# ver061_Power.net
KiCad netlist of a schematic drawn in Altium Designer
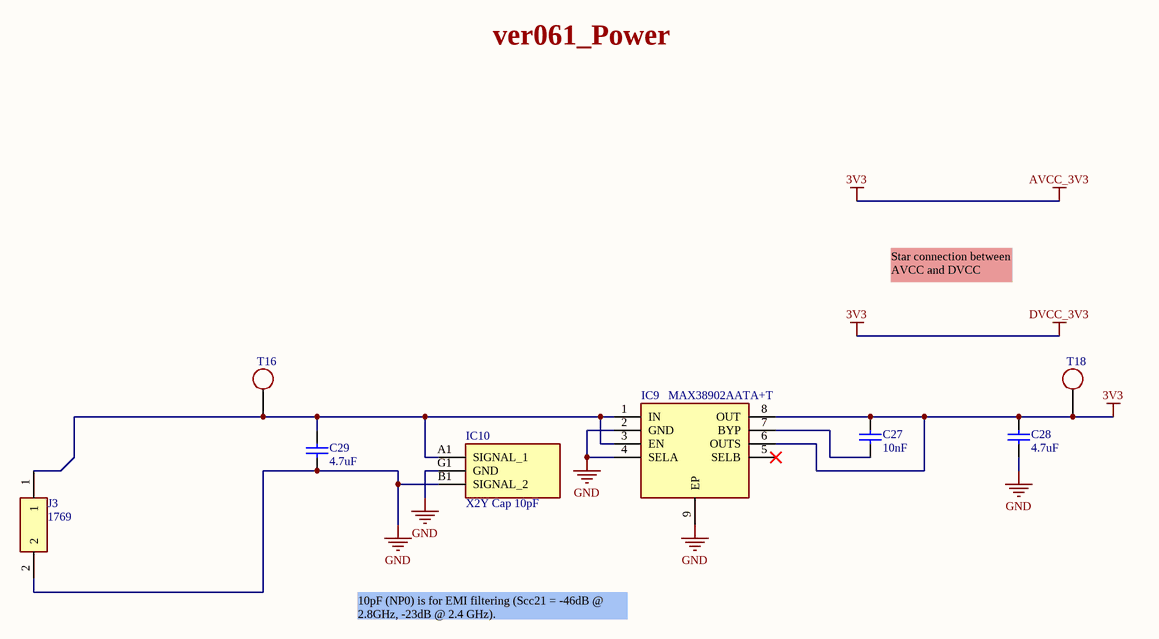
[diagram p0: ver061_Power.SchDoc]

(export (version "E")
  (design (tool "Eeschema 10.0.6"))
  (components
    (comp (ref "C27")
      (value "10nF")
      (footprint "0402")
      (description "Capacitor (Semiconductor SIM Model)")
      (fields (field (name "Comment") "Cap Semi") (field (name "PUBLISHER") "Altium Limited"))
      (libsource (lib "Miscellaneous Devices") (part "Cap Semi"))
    )
    (comp (ref "C28")
      (value "4.7uF")
      (footprint "0402")
      (description "Capacitor (Semiconductor SIM Model)")
      (fields (field (name "Comment") "Cap Semi") (field (name "PUBLISHER") "Altium Limited"))
      (libsource (lib "Miscellaneous Devices") (part "Cap Semi"))
    )
    (comp (ref "C29")
      (value "4.7uF")
      (footprint "0402")
      (description "Capacitor (Semiconductor SIM Model)")
      (fields (field (name "Comment") "Cap Semi") (field (name "PUBLISHER") "Altium Limited"))
      (libsource (lib "Miscellaneous Devices") (part "Cap Semi"))
    )
    (comp (ref "IC9")
      (value "MAX38902AATA+T")
      (footprint "nanowire:SON50P200X200X80-9N-D")
      (description "Integrated Circuit")
      (fields (field (name "MOUSER PART NUMBER") "700-MAX38902AATA+T"))
      (libsource (lib "*") (part "MAX38902AATA+T"))
    )
    (comp (ref "IC10")
      (value "X2Y Cap 10pF")
      (footprint "500X14W102MV4T")
      (description "Integrated Circuit")
      (fields
        (field (name "MANUFACTURER_PART_NUMBER") "500X14W102MV4T")
        (field (name "MOUSER PART NUMBER") "605-500X14W102MV4T")
      )
      (libsource (lib "nanowire") (part "500X14W102MV4T"))
    )
    (comp (ref "J3")
      (value "1769")
      (footprint "nanowire:1769")
      (description "Connector")
      (fields (field (name "MOUSER PART NUMBER") "485-1769"))
      (libsource (lib "*") (part "1769"))
    )
    (comp (ref "T16")
      (value "TP_SMT")
      (footprint "TP_SMT_Round_0.6x0.6")
      (libsource (lib "nanowire") (part "TP_SMT"))
    )
    (comp (ref "T18")
      (value "TP_SMT")
      (footprint "TP_SMT_Round_0.6x0.6")
      (libsource (lib "nanowire") (part "TP_SMT"))
    )
  )
  (nets
    (net (code "1") (name "3V3") (class "Default")
      (node (ref "C27") (pin "1") (pinfunction "1_1") (pintype "passive"))
      (node (ref "C28") (pin "1") (pinfunction "1_1") (pintype "passive"))
      (node (ref "IC9") (pin "6") (pinfunction "OUTS_6") (pintype "passive"))
      (node (ref "IC9") (pin "8") (pinfunction "OUT_8") (pintype "passive"))
      (node (ref "T18") (pin "1") (pinfunction "1_1") (pintype "passive"))
    )
    (net (code "2") (name "GND") (class "Default")
      (node (ref "C28") (pin "2") (pinfunction "2_2") (pintype "passive"))
      (node (ref "C29") (pin "2") (pinfunction "2_2") (pintype "passive"))
      (node (ref "IC10") (pin "B1") (pinfunction "SIGNAL_2_B1") (pintype "passive"))
      (node (ref "IC10") (pin "G1") (pinfunction "GND_G1") (pintype "passive"))
      (node (ref "IC9") (pin "2") (pinfunction "GND_2") (pintype "passive"))
      (node (ref "IC9") (pin "4") (pinfunction "SELA_4") (pintype "passive"))
      (node (ref "IC9") (pin "9") (pinfunction "EP_9") (pintype "passive"))
      (node (ref "J3") (pin "2") (pinfunction "2_2") (pintype "passive"))
    )
    (net (code "3") (name "Net-(IC9-BYP)") (class "Default")
      (node (ref "C27") (pin "2") (pinfunction "2_2") (pintype "passive"))
      (node (ref "IC9") (pin "7") (pinfunction "BYP_7") (pintype "passive"))
    )
    (net (code "4") (name "Net-(IC10-SIGNAL_1)") (class "Default")
      (node (ref "C29") (pin "1") (pinfunction "1_1") (pintype "passive"))
      (node (ref "IC10") (pin "A1") (pinfunction "SIGNAL_1_A1") (pintype "passive"))
      (node (ref "IC9") (pin "1") (pinfunction "IN_1") (pintype "passive"))
      (node (ref "IC9") (pin "3") (pinfunction "EN_3") (pintype "passive"))
      (node (ref "J3") (pin "1") (pinfunction "1_1") (pintype "passive"))
      (node (ref "T16") (pin "1") (pinfunction "1_1") (pintype "passive"))
    )
    (net (code "5") (name "unconnected-(IC9-SELB-Pad5)") (class "Default")
      (node (ref "IC9") (pin "5") (pinfunction "SELB_5") (pintype "passive+no_connect"))
    )
  )
)
